# Core.net
KiCad netlist of a schematic drawn in Altium Designer
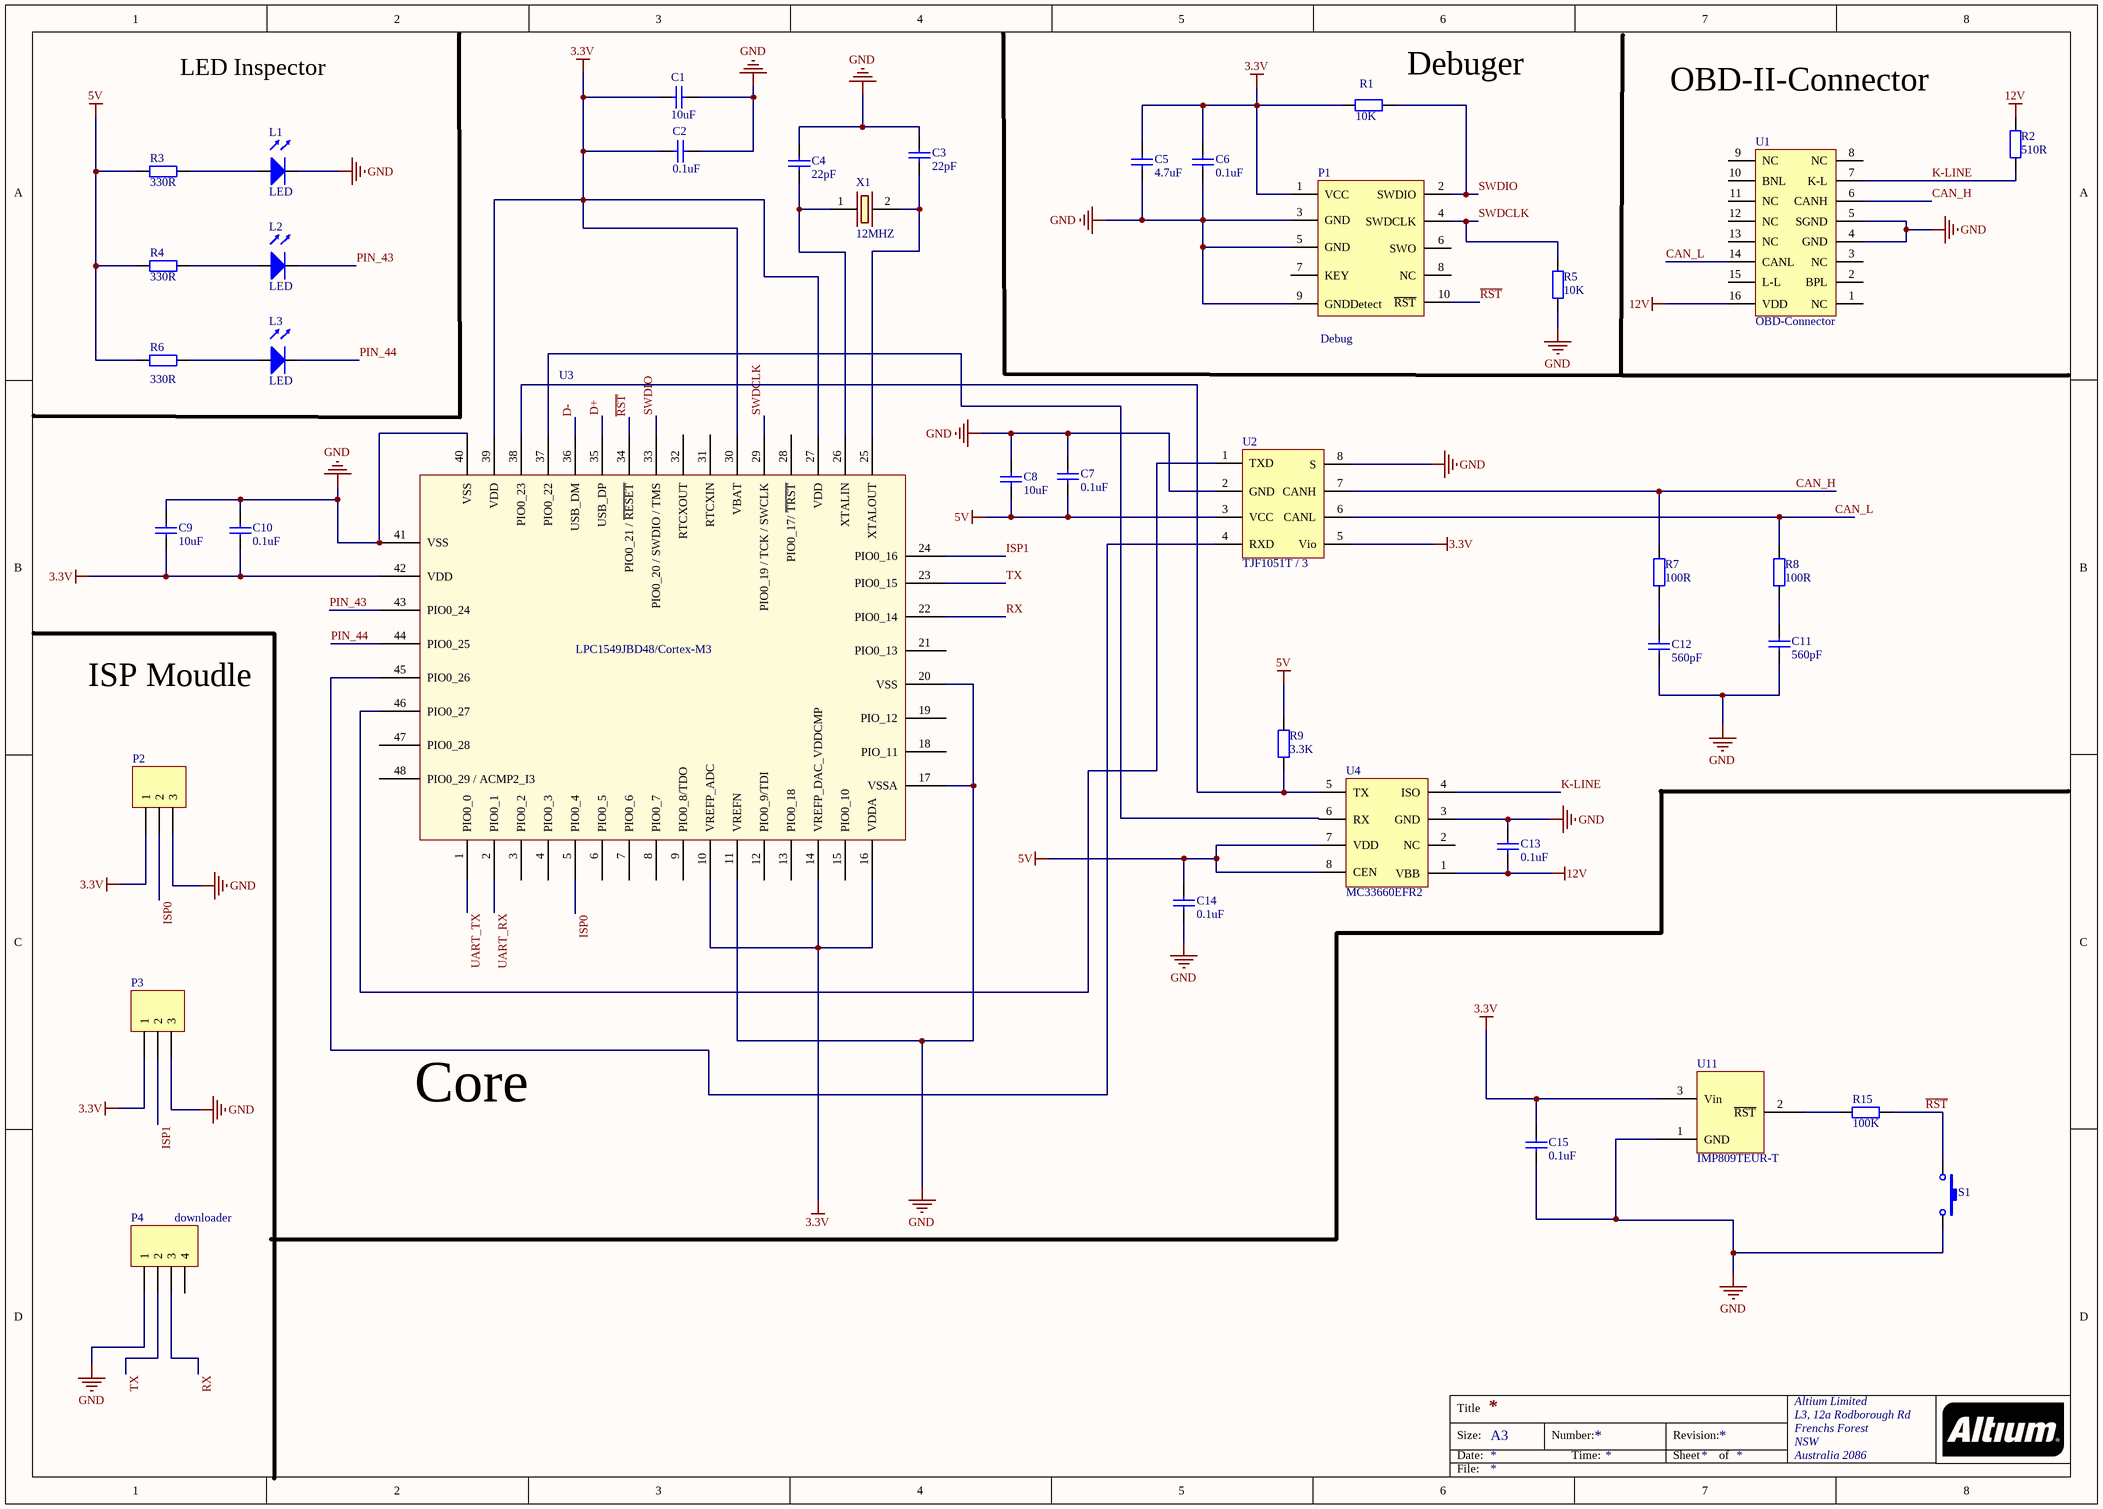
[diagram p0: Core.SchDoc]

(export (version "E")
  (design (tool "Eeschema 10.0.6"))
  (components
    (comp (ref "C1")
      (value "10uF")
      (footprint "0603")
      (description "ceramic")
      (libsource (lib "ToponLib") (part "Cap1"))
    )
    (comp (ref "C2")
      (value "0.1uF")
      (footprint "0603")
      (description "ceramic")
      (libsource (lib "ToponLib") (part "Cap1"))
    )
    (comp (ref "C3")
      (value "22pF")
      (footprint "0603")
      (description "ceramic")
      (libsource (lib "ToponLib") (part "Cap1"))
    )
    (comp (ref "C4")
      (value "22pF")
      (footprint "0603")
      (description "ceramic")
      (libsource (lib "ToponLib") (part "Cap1"))
    )
    (comp (ref "C5")
      (value "4.7uF")
      (footprint "0603")
      (description "ceramic")
      (libsource (lib "ToponLib") (part "Cap1"))
    )
    (comp (ref "C6")
      (value "0.1uF")
      (footprint "0603")
      (description "ceramic")
      (libsource (lib "ToponLib") (part "Cap1"))
    )
    (comp (ref "C7")
      (value "0.1uF")
      (footprint "0603")
      (description "ceramic")
      (libsource (lib "ToponLib") (part "Cap1"))
    )
    (comp (ref "C8")
      (value "10uF")
      (footprint "0603")
      (description "ceramic")
      (libsource (lib "ToponLib") (part "Cap1"))
    )
    (comp (ref "C9")
      (value "10uF")
      (footprint "0603")
      (description "ceramic")
      (libsource (lib "ToponLib") (part "Cap1"))
    )
    (comp (ref "C10")
      (value "0.1uF")
      (footprint "0603")
      (description "ceramic")
      (libsource (lib "ToponLib") (part "Cap1"))
    )
    (comp (ref "C11")
      (value "560pF")
      (footprint "0603")
      (description "ceramic")
      (libsource (lib "ToponLib") (part "Cap1"))
    )
    (comp (ref "C12")
      (value "560pF")
      (footprint "0603")
      (description "ceramic")
      (libsource (lib "ToponLib") (part "Cap1"))
    )
    (comp (ref "C13")
      (value "0.1uF")
      (footprint "0603")
      (description "ceramic")
      (libsource (lib "ToponLib") (part "Cap1"))
    )
    (comp (ref "C14")
      (value "0.1uF")
      (footprint "0603")
      (description "ceramic")
      (libsource (lib "ToponLib") (part "Cap1"))
    )
    (comp (ref "C15")
      (value "0.1uF")
      (footprint "0603")
      (description "ceramic")
      (libsource (lib "ToponLib") (part "Cap1"))
    )
    (comp (ref "L1") (value "LED") (footprint "0805") (libsource (lib "ToponLib") (part "LED")))
    (comp (ref "L2") (value "LED") (footprint "0805") (libsource (lib "ToponLib") (part "LED")))
    (comp (ref "L3") (value "LED") (footprint "0805") (libsource (lib "ToponLib") (part "LED")))
    (comp (ref "P1")
      (value "Debug")
      (footprint "JATG_10pin")
      (libsource (lib "ToponLib") (part "JTAG_10Pin"))
    )
    (comp (ref "P2")
      (value "~")
      (footprint "HDR1X3")
      (description "Header, 3-Pin")
      (fields (field (name "PUBLISHER") "Altium Limited"))
      (libsource (lib "Miscellaneous Connectors") (part "Header 3"))
    )
    (comp (ref "P3")
      (value "~")
      (footprint "HDR1X3")
      (description "Header, 3-Pin")
      (fields (field (name "PUBLISHER") "Altium Limited"))
      (libsource (lib "Miscellaneous Connectors") (part "Header 3"))
    )
    (comp (ref "P4")
      (value "downloader")
      (footprint "HDR1X4")
      (description "Header, 4-Pin")
      (fields (field (name "PUBLISHER") "Altium Limited"))
      (libsource (lib "Miscellaneous Connectors") (part "Header 4"))
    )
    (comp (ref "R1") (value "10K") (footprint "0603") (libsource (lib "ToponLib") (part "Res")))
    (comp (ref "R2") (value "510R") (footprint "0603") (libsource (lib "") (part "Res_1")))
    (comp (ref "R3") (value "330R") (footprint "0603") (libsource (lib "ToponLib") (part "Res")))
    (comp (ref "R4") (value "330R") (footprint "0603") (libsource (lib "ToponLib") (part "Res")))
    (comp (ref "R5") (value "10K") (footprint "0603") (libsource (lib "") (part "Res_1")))
    (comp (ref "R6") (value "330R") (footprint "0603") (libsource (lib "ToponLib") (part "Res")))
    (comp (ref "R7") (value "100R") (footprint "0603") (libsource (lib "") (part "Res_1")))
    (comp (ref "R8") (value "100R") (footprint "0603") (libsource (lib "") (part "Res_1")))
    (comp (ref "R9") (value "3.3K") (footprint "0603") (libsource (lib "") (part "Res_1")))
    (comp (ref "R15") (value "100K") (footprint "0603") (libsource (lib "") (part "Res_2")))
    (comp (ref "S1") (value "Button") (footprint "BUtton-T4") (libsource (lib "ToponLib") (part "Button")))
    (comp (ref "U1")
      (value "OBD-Connector")
      (footprint "OBD-Female")
      (libsource (lib "ToponLib") (part "OBD-MaleHead"))
    )
    (comp (ref "U2")
      (value "TJF1051T / 3")
      (footprint "TJF1051")
      (libsource (lib "ToponLib") (part "TJF1051T / 3"))
    )
    (comp (ref "U3")
      (value "LPC1549")
      (footprint "LPC1549JBD48")
      (libsource (lib "ToponLib") (part "LPC1549JBD48"))
    )
    (comp (ref "U4")
      (value "MC33660EFR2")
      (footprint "SOP-8")
      (libsource (lib "ToponLib") (part "MC33660EFR2"))
    )
    (comp (ref "U11")
      (value "IMP809TEUR-T")
      (footprint "SOT23-3")
      (libsource (lib "ToponLib") (part "IMP809TEUR-T"))
    )
    (comp (ref "X1") (value "12MHZ") (footprint "12Mhz-DFN") (libsource (lib "ToponLib") (part "OSC")))
  )
  (nets
    (net (code "1") (name "/CAN_H") (class "Default")
      (node (ref "R7") (pin "2") (pinfunction "2_2") (pintype "passive"))
      (node (ref "U1") (pin "6") (pinfunction "CANH_6") (pintype "passive"))
      (node (ref "U2") (pin "7") (pinfunction "CANH_7") (pintype "passive"))
    )
    (net (code "2") (name "/CAN_L") (class "Default")
      (node (ref "R8") (pin "2") (pinfunction "2_2") (pintype "passive"))
      (node (ref "U1") (pin "14") (pinfunction "CANL_14") (pintype "passive"))
      (node (ref "U2") (pin "6") (pinfunction "CANL_6") (pintype "passive"))
    )
    (net (code "3") (name "/D+") (class "Default")
      (node (ref "U3") (pin "35") (pinfunction "USB_DP_35") (pintype "passive"))
    )
    (net (code "4") (name "/D-") (class "Default")
      (node (ref "U3") (pin "36") (pinfunction "USB_DM_36") (pintype "passive"))
    )
    (net (code "5") (name "/ISP0") (class "Default")
      (node (ref "P2") (pin "2") (pinfunction "2_2") (pintype "passive"))
      (node (ref "U3") (pin "5") (pinfunction "PIO0_4_5") (pintype "passive"))
    )
    (net (code "6") (name "/ISP1") (class "Default")
      (node (ref "P3") (pin "2") (pinfunction "2_2") (pintype "passive"))
      (node (ref "U3") (pin "24") (pinfunction "PIO0_16_24") (pintype "passive"))
    )
    (net (code "7") (name "/K-LINE") (class "Default")
      (node (ref "R2") (pin "1") (pinfunction "1_1") (pintype "passive"))
      (node (ref "U1") (pin "7") (pinfunction "K-L_7") (pintype "passive"))
      (node (ref "U4") (pin "4") (pinfunction "ISO_4") (pintype "passive"))
    )
    (net (code "8") (name "/PIN_43") (class "Default")
      (node (ref "L2") (pin "2") (pinfunction "K_2") (pintype "passive"))
      (node (ref "U3") (pin "43") (pinfunction "PIO0_24_43") (pintype "passive"))
    )
    (net (code "9") (name "/PIN_44") (class "Default")
      (node (ref "L3") (pin "2") (pinfunction "K_2") (pintype "passive"))
      (node (ref "U3") (pin "44") (pinfunction "PIO0_25_44") (pintype "passive"))
    )
    (net (code "10") (name "/RX") (class "Default")
      (node (ref "P4") (pin "3") (pinfunction "3_3") (pintype "passive"))
      (node (ref "U3") (pin "22") (pinfunction "PIO0_14_22") (pintype "passive"))
    )
    (net (code "11") (name "/SWDCLK") (class "Default")
      (node (ref "P1") (pin "4") (pinfunction "SWDCLK_4") (pintype "passive"))
      (node (ref "R5") (pin "2") (pinfunction "2_2") (pintype "passive"))
      (node (ref "U3") (pin "29") (pinfunction "PIO0_19_/_TCK_/_SWCLK_29") (pintype "passive"))
    )
    (net (code "12") (name "/SWDIO") (class "Default")
      (node (ref "P1") (pin "2") (pinfunction "SWDIO_2") (pintype "passive"))
      (node (ref "R1") (pin "2") (pinfunction "2_2") (pintype "passive"))
      (node (ref "U3") (pin "33") (pinfunction "PIO0_20_/_SWDIO_/_TMS_33") (pintype "passive"))
    )
    (net (code "13") (name "/TX") (class "Default")
      (node (ref "P4") (pin "2") (pinfunction "2_2") (pintype "passive"))
      (node (ref "U3") (pin "23") (pinfunction "PIO0_15_23") (pintype "passive"))
    )
    (net (code "14") (name "/UART_RX") (class "Default")
      (node (ref "U3") (pin "2") (pinfunction "PIO0_1_2") (pintype "passive"))
    )
    (net (code "15") (name "/UART_TX") (class "Default")
      (node (ref "U3") (pin "1") (pinfunction "PIO0_0_1") (pintype "passive"))
    )
    (net (code "16") (name "/~{RST}") (class "Default")
      (node (ref "P1") (pin "10") (pinfunction "~{RST}_10") (pintype "passive"))
      (node (ref "R15") (pin "1") (pinfunction "1_1") (pintype "passive"))
      (node (ref "S1") (pin "1") (pinfunction "1_1") (pintype "passive"))
      (node (ref "U3") (pin "34") (pinfunction "PIO0_21_/_~{RESET}_34") (pintype "passive"))
    )
    (net (code "17") (name "3.3V") (class "Default")
      (node (ref "C1") (pin "2") (pinfunction "2_2") (pintype "passive"))
      (node (ref "C10") (pin "1") (pinfunction "1_1") (pintype "passive"))
      (node (ref "C15") (pin "2") (pinfunction "2_2") (pintype "passive"))
      (node (ref "C2") (pin "2") (pinfunction "2_2") (pintype "passive"))
      (node (ref "C5") (pin "2") (pinfunction "2_2") (pintype "passive"))
      (node (ref "C6") (pin "2") (pinfunction "2_2") (pintype "passive"))
      (node (ref "C9") (pin "1") (pinfunction "1_1") (pintype "passive"))
      (node (ref "P1") (pin "1") (pinfunction "VCC_1") (pintype "passive"))
      (node (ref "P2") (pin "1") (pinfunction "1_1") (pintype "passive"))
      (node (ref "P3") (pin "1") (pinfunction "1_1") (pintype "passive"))
      (node (ref "R1") (pin "1") (pinfunction "1_1") (pintype "passive"))
      (node (ref "U11") (pin "3") (pinfunction "Vin_3") (pintype "passive"))
      (node (ref "U2") (pin "5") (pinfunction "Vio_5") (pintype "passive"))
      (node (ref "U3") (pin "10") (pinfunction "VREFP_ADC_10") (pintype "passive"))
      (node (ref "U3") (pin "14") (pinfunction "VREFP_DAC_VDDCMP_14") (pintype "passive"))
      (node (ref "U3") (pin "16") (pinfunction "VDDA_16") (pintype "passive"))
      (node (ref "U3") (pin "27") (pinfunction "VDD_27") (pintype "passive"))
      (node (ref "U3") (pin "30") (pinfunction "VBAT_30") (pintype "passive"))
      (node (ref "U3") (pin "39") (pinfunction "VDD_39") (pintype "passive"))
      (node (ref "U3") (pin "42") (pinfunction "VDD_42") (pintype "passive"))
    )
    (net (code "18") (name "5V") (class "Default")
      (node (ref "C14") (pin "2") (pinfunction "2_2") (pintype "passive"))
      (node (ref "C7") (pin "1") (pinfunction "1_1") (pintype "passive"))
      (node (ref "C8") (pin "1") (pinfunction "1_1") (pintype "passive"))
      (node (ref "R3") (pin "1") (pinfunction "1_1") (pintype "passive"))
      (node (ref "R4") (pin "1") (pinfunction "1_1") (pintype "passive"))
      (node (ref "R6") (pin "1") (pinfunction "1_1") (pintype "passive"))
      (node (ref "R9") (pin "2") (pinfunction "2_2") (pintype "passive"))
      (node (ref "U2") (pin "3") (pinfunction "VCC_3") (pintype "passive"))
      (node (ref "U4") (pin "7") (pinfunction "VDD_7") (pintype "passive"))
      (node (ref "U4") (pin "8") (pinfunction "CEN_8") (pintype "passive"))
    )
    (net (code "19") (name "12V") (class "Default")
      (node (ref "C13") (pin "1") (pinfunction "1_1") (pintype "passive"))
      (node (ref "R2") (pin "2") (pinfunction "2_2") (pintype "passive"))
      (node (ref "U1") (pin "16") (pinfunction "VDD_16") (pintype "passive"))
      (node (ref "U4") (pin "1") (pinfunction "VBB_1") (pintype "passive"))
    )
    (net (code "20") (name "GND") (class "Default")
      (node (ref "C1") (pin "1") (pinfunction "1_1") (pintype "passive"))
      (node (ref "C10") (pin "2") (pinfunction "2_2") (pintype "passive"))
      (node (ref "C11") (pin "1") (pinfunction "1_1") (pintype "passive"))
      (node (ref "C12") (pin "1") (pinfunction "1_1") (pintype "passive"))
      (node (ref "C13") (pin "2") (pinfunction "2_2") (pintype "passive"))
      (node (ref "C14") (pin "1") (pinfunction "1_1") (pintype "passive"))
      (node (ref "C15") (pin "1") (pinfunction "1_1") (pintype "passive"))
      (node (ref "C2") (pin "1") (pinfunction "1_1") (pintype "passive"))
      (node (ref "C3") (pin "2") (pinfunction "2_2") (pintype "passive"))
      (node (ref "C4") (pin "2") (pinfunction "2_2") (pintype "passive"))
      (node (ref "C5") (pin "1") (pinfunction "1_1") (pintype "passive"))
      (node (ref "C6") (pin "1") (pinfunction "1_1") (pintype "passive"))
      (node (ref "C7") (pin "2") (pinfunction "2_2") (pintype "passive"))
      (node (ref "C8") (pin "2") (pinfunction "2_2") (pintype "passive"))
      (node (ref "C9") (pin "2") (pinfunction "2_2") (pintype "passive"))
      (node (ref "L1") (pin "2") (pinfunction "K_2") (pintype "passive"))
      (node (ref "P1") (pin "3") (pinfunction "GND_3") (pintype "passive"))
      (node (ref "P1") (pin "5") (pinfunction "GND_5") (pintype "passive"))
      (node (ref "P1") (pin "9") (pinfunction "GNDDetect_9") (pintype "passive"))
      (node (ref "P2") (pin "3") (pinfunction "3_3") (pintype "passive"))
      (node (ref "P3") (pin "3") (pinfunction "3_3") (pintype "passive"))
      (node (ref "P4") (pin "1") (pinfunction "1_1") (pintype "passive"))
      (node (ref "R5") (pin "1") (pinfunction "1_1") (pintype "passive"))
      (node (ref "S1") (pin "2") (pinfunction "2_2") (pintype "passive"))
      (node (ref "U1") (pin "4") (pinfunction "GND_4") (pintype "passive"))
      (node (ref "U1") (pin "5") (pinfunction "SGND_5") (pintype "passive"))
      (node (ref "U11") (pin "1") (pinfunction "GND_1") (pintype "passive"))
      (node (ref "U2") (pin "2") (pinfunction "GND_2") (pintype "passive"))
      (node (ref "U2") (pin "8") (pinfunction "S_8") (pintype "passive"))
      (node (ref "U3") (pin "11") (pinfunction "VREFN_11") (pintype "passive"))
      (node (ref "U3") (pin "17") (pinfunction "VSSA_17") (pintype "passive"))
      (node (ref "U3") (pin "20") (pinfunction "VSS_20") (pintype "passive"))
      (node (ref "U3") (pin "40") (pinfunction "VSS_40") (pintype "passive"))
      (node (ref "U3") (pin "41") (pinfunction "VSS_41") (pintype "passive"))
      (node (ref "U4") (pin "3") (pinfunction "GND_3") (pintype "passive"))
    )
    (net (code "21") (name "Net-(C11-Pad2)") (class "Default")
      (node (ref "C11") (pin "2") (pinfunction "2_2") (pintype "passive"))
      (node (ref "R8") (pin "1") (pinfunction "1_1") (pintype "passive"))
    )
    (net (code "22") (name "Net-(C12-Pad2)") (class "Default")
      (node (ref "C12") (pin "2") (pinfunction "2_2") (pintype "passive"))
      (node (ref "R7") (pin "1") (pinfunction "1_1") (pintype "passive"))
    )
    (net (code "23") (name "Net-(L1-A)") (class "Default")
      (node (ref "L1") (pin "1") (pinfunction "A_1") (pintype "passive"))
      (node (ref "R3") (pin "2") (pinfunction "2_2") (pintype "passive"))
    )
    (net (code "24") (name "Net-(L2-A)") (class "Default")
      (node (ref "L2") (pin "1") (pinfunction "A_1") (pintype "passive"))
      (node (ref "R4") (pin "2") (pinfunction "2_2") (pintype "passive"))
    )
    (net (code "25") (name "Net-(L3-A)") (class "Default")
      (node (ref "L3") (pin "1") (pinfunction "A_1") (pintype "passive"))
      (node (ref "R6") (pin "2") (pinfunction "2_2") (pintype "passive"))
    )
    (net (code "26") (name "Net-(U2-RXD)") (class "Default")
      (node (ref "U2") (pin "4") (pinfunction "RXD_4") (pintype "passive"))
      (node (ref "U3") (pin "45") (pinfunction "PIO0_26_45") (pintype "passive"))
    )
    (net (code "27") (name "Net-(U2-TXD)") (class "Default")
      (node (ref "U2") (pin "1") (pinfunction "TXD_1") (pintype "passive"))
      (node (ref "U3") (pin "46") (pinfunction "PIO0_27_46") (pintype "passive"))
    )
    (net (code "28") (name "Net-(U3-PIO0_22)") (class "Default")
      (node (ref "U3") (pin "37") (pinfunction "PIO0_22_37") (pintype "passive"))
      (node (ref "U4") (pin "6") (pinfunction "RX_6") (pintype "passive"))
    )
    (net (code "29") (name "Net-(U3-PIO0_23)") (class "Default")
      (node (ref "R9") (pin "1") (pinfunction "1_1") (pintype "passive"))
      (node (ref "U3") (pin "38") (pinfunction "PIO0_23_38") (pintype "passive"))
      (node (ref "U4") (pin "5") (pinfunction "TX_5") (pintype "passive"))
    )
    (net (code "30") (name "Net-(U3-XTALIN)") (class "Default")
      (node (ref "C4") (pin "1") (pinfunction "1_1") (pintype "passive"))
      (node (ref "U3") (pin "26") (pinfunction "XTALIN_26") (pintype "passive"))
      (node (ref "X1") (pin "1") (pinfunction "1_1") (pintype "passive"))
    )
    (net (code "31") (name "Net-(U3-XTALOUT)") (class "Default")
      (node (ref "C3") (pin "1") (pinfunction "1_1") (pintype "passive"))
      (node (ref "U3") (pin "25") (pinfunction "XTALOUT_25") (pintype "passive"))
      (node (ref "X1") (pin "2") (pinfunction "2_2") (pintype "passive"))
    )
    (net (code "32") (name "Net-(U11-~{RST})") (class "Default")
      (node (ref "R15") (pin "2") (pinfunction "2_2") (pintype "passive"))
      (node (ref "U11") (pin "2") (pinfunction "~{RST}_2") (pintype "passive"))
    )
    (net (code "33") (name "unconnected-(P1-KEY-Pad7)") (class "Default")
      (node (ref "P1") (pin "7") (pinfunction "KEY_7") (pintype "passive"))
    )
    (net (code "34") (name "unconnected-(P1-NC-Pad8)") (class "Default")
      (node (ref "P1") (pin "8") (pinfunction "NC_8") (pintype "passive"))
    )
    (net (code "35") (name "unconnected-(P1-SWO-Pad6)") (class "Default")
      (node (ref "P1") (pin "6") (pinfunction "SWO_6") (pintype "passive"))
    )
    (net (code "36") (name "unconnected-(P4-Pad4)") (class "Default")
      (node (ref "P4") (pin "4") (pinfunction "4_4") (pintype "passive"))
    )
    (net (code "37") (name "unconnected-(U1-BNL-Pad10)") (class "Default")
      (node (ref "U1") (pin "10") (pinfunction "BNL_10") (pintype "passive"))
    )
    (net (code "38") (name "unconnected-(U1-BPL-Pad2)") (class "Default")
      (node (ref "U1") (pin "2") (pinfunction "BPL_2") (pintype "passive"))
    )
    (net (code "39") (name "unconnected-(U1-L-L-Pad15)") (class "Default")
      (node (ref "U1") (pin "15") (pinfunction "L-L_15") (pintype "passive"))
    )
    (net (code "40") (name "unconnected-(U1-NC-Pad1)") (class "Default")
      (node (ref "U1") (pin "1") (pinfunction "NC_1") (pintype "passive"))
    )
    (net (code "41") (name "unconnected-(U1-NC-Pad3)") (class "Default")
      (node (ref "U1") (pin "3") (pinfunction "NC_3") (pintype "passive"))
    )
    (net (code "42") (name "unconnected-(U1-NC-Pad8)") (class "Default")
      (node (ref "U1") (pin "8") (pinfunction "NC_8") (pintype "passive"))
    )
    (net (code "43") (name "unconnected-(U1-NC-Pad9)") (class "Default")
      (node (ref "U1") (pin "9") (pinfunction "NC_9") (pintype "passive"))
    )
    (net (code "44") (name "unconnected-(U1-NC-Pad11)") (class "Default")
      (node (ref "U1") (pin "11") (pinfunction "NC_11") (pintype "passive"))
    )
    (net (code "45") (name "unconnected-(U1-NC-Pad12)") (class "Default")
      (node (ref "U1") (pin "12") (pinfunction "NC_12") (pintype "passive"))
    )
    (net (code "46") (name "unconnected-(U1-NC-Pad13)") (class "Default")
      (node (ref "U1") (pin "13") (pinfunction "NC_13") (pintype "passive"))
    )
    (net (code "47") (name "unconnected-(U3-PIO0_2-Pad3)") (class "Default")
      (node (ref "U3") (pin "3") (pinfunction "PIO0_2_3") (pintype "passive"))
    )
    (net (code "48") (name "unconnected-(U3-PIO0_3-Pad4)") (class "Default")
      (node (ref "U3") (pin "4") (pinfunction "PIO0_3_4") (pintype "passive"))
    )
    (net (code "49") (name "unconnected-(U3-PIO0_5-Pad6)") (class "Default")
      (node (ref "U3") (pin "6") (pinfunction "PIO0_5_6") (pintype "passive"))
    )
    (net (code "50") (name "unconnected-(U3-PIO0_6-Pad7)") (class "Default")
      (node (ref "U3") (pin "7") (pinfunction "PIO0_6_7") (pintype "passive"))
    )
    (net (code "51") (name "unconnected-(U3-PIO0_7-Pad8)") (class "Default")
      (node (ref "U3") (pin "8") (pinfunction "PIO0_7_8") (pintype "passive"))
    )
    (net (code "52") (name "unconnected-(U3-PIO0_8{slash}TDO-Pad9)") (class "Default")
      (node (ref "U3") (pin "9") (pinfunction "PIO0_8/TDO_9") (pintype "passive"))
    )
    (net (code "53") (name "unconnected-(U3-PIO0_9{slash}TDI-Pad12)") (class "Default")
      (node (ref "U3") (pin "12") (pinfunction "PIO0_9/TDI_12") (pintype "passive"))
    )
    (net (code "54") (name "unconnected-(U3-PIO0_10-Pad15)") (class "Default")
      (node (ref "U3") (pin "15") (pinfunction "PIO0_10_15") (pintype "passive"))
    )
    (net (code "55") (name "unconnected-(U3-PIO0_13-Pad21)") (class "Default")
      (node (ref "U3") (pin "21") (pinfunction "PIO0_13_21") (pintype "passive"))
    )
    (net (code "56") (name "unconnected-(U3-PIO0_17{slash}_~{TRST}-Pad28)") (class "Default")
      (node (ref "U3") (pin "28") (pinfunction "PIO0_17/_~{TRST}_28") (pintype "passive"))
    )
    (net (code "57") (name "unconnected-(U3-PIO0_18-Pad13)") (class "Default")
      (node (ref "U3") (pin "13") (pinfunction "PIO0_18_13") (pintype "passive"))
    )
    (net (code "58") (name "unconnected-(U3-PIO0_28-Pad47)") (class "Default")
      (node (ref "U3") (pin "47") (pinfunction "PIO0_28_47") (pintype "passive"))
    )
    (net (code "59") (name "unconnected-(U3-PIO0_29_{slash}_ACMP2_I3-Pad48)") (class "Default")
      (node (ref "U3") (pin "48") (pinfunction "PIO0_29_/_ACMP2_I3_48") (pintype "passive"))
    )
    (net (code "60") (name "unconnected-(U3-PIO_11-Pad18)") (class "Default")
      (node (ref "U3") (pin "18") (pinfunction "PIO_11_18") (pintype "passive"))
    )
    (net (code "61") (name "unconnected-(U3-PIO_12-Pad19)") (class "Default")
      (node (ref "U3") (pin "19") (pinfunction "PIO_12_19") (pintype "passive"))
    )
    (net (code "62") (name "unconnected-(U3-RTCXIN-Pad31)") (class "Default")
      (node (ref "U3") (pin "31") (pinfunction "RTCXIN_31") (pintype "passive"))
    )
    (net (code "63") (name "unconnected-(U3-RTCXOUT-Pad32)") (class "Default")
      (node (ref "U3") (pin "32") (pinfunction "RTCXOUT_32") (pintype "passive"))
    )
    (net (code "64") (name "unconnected-(U4-NC-Pad2)") (class "Default")
      (node (ref "U4") (pin "2") (pinfunction "NC_2") (pintype "passive"))
    )
  )
)
